# 1_1.net
KiCad netlist of a schematic drawn in Altium Designer
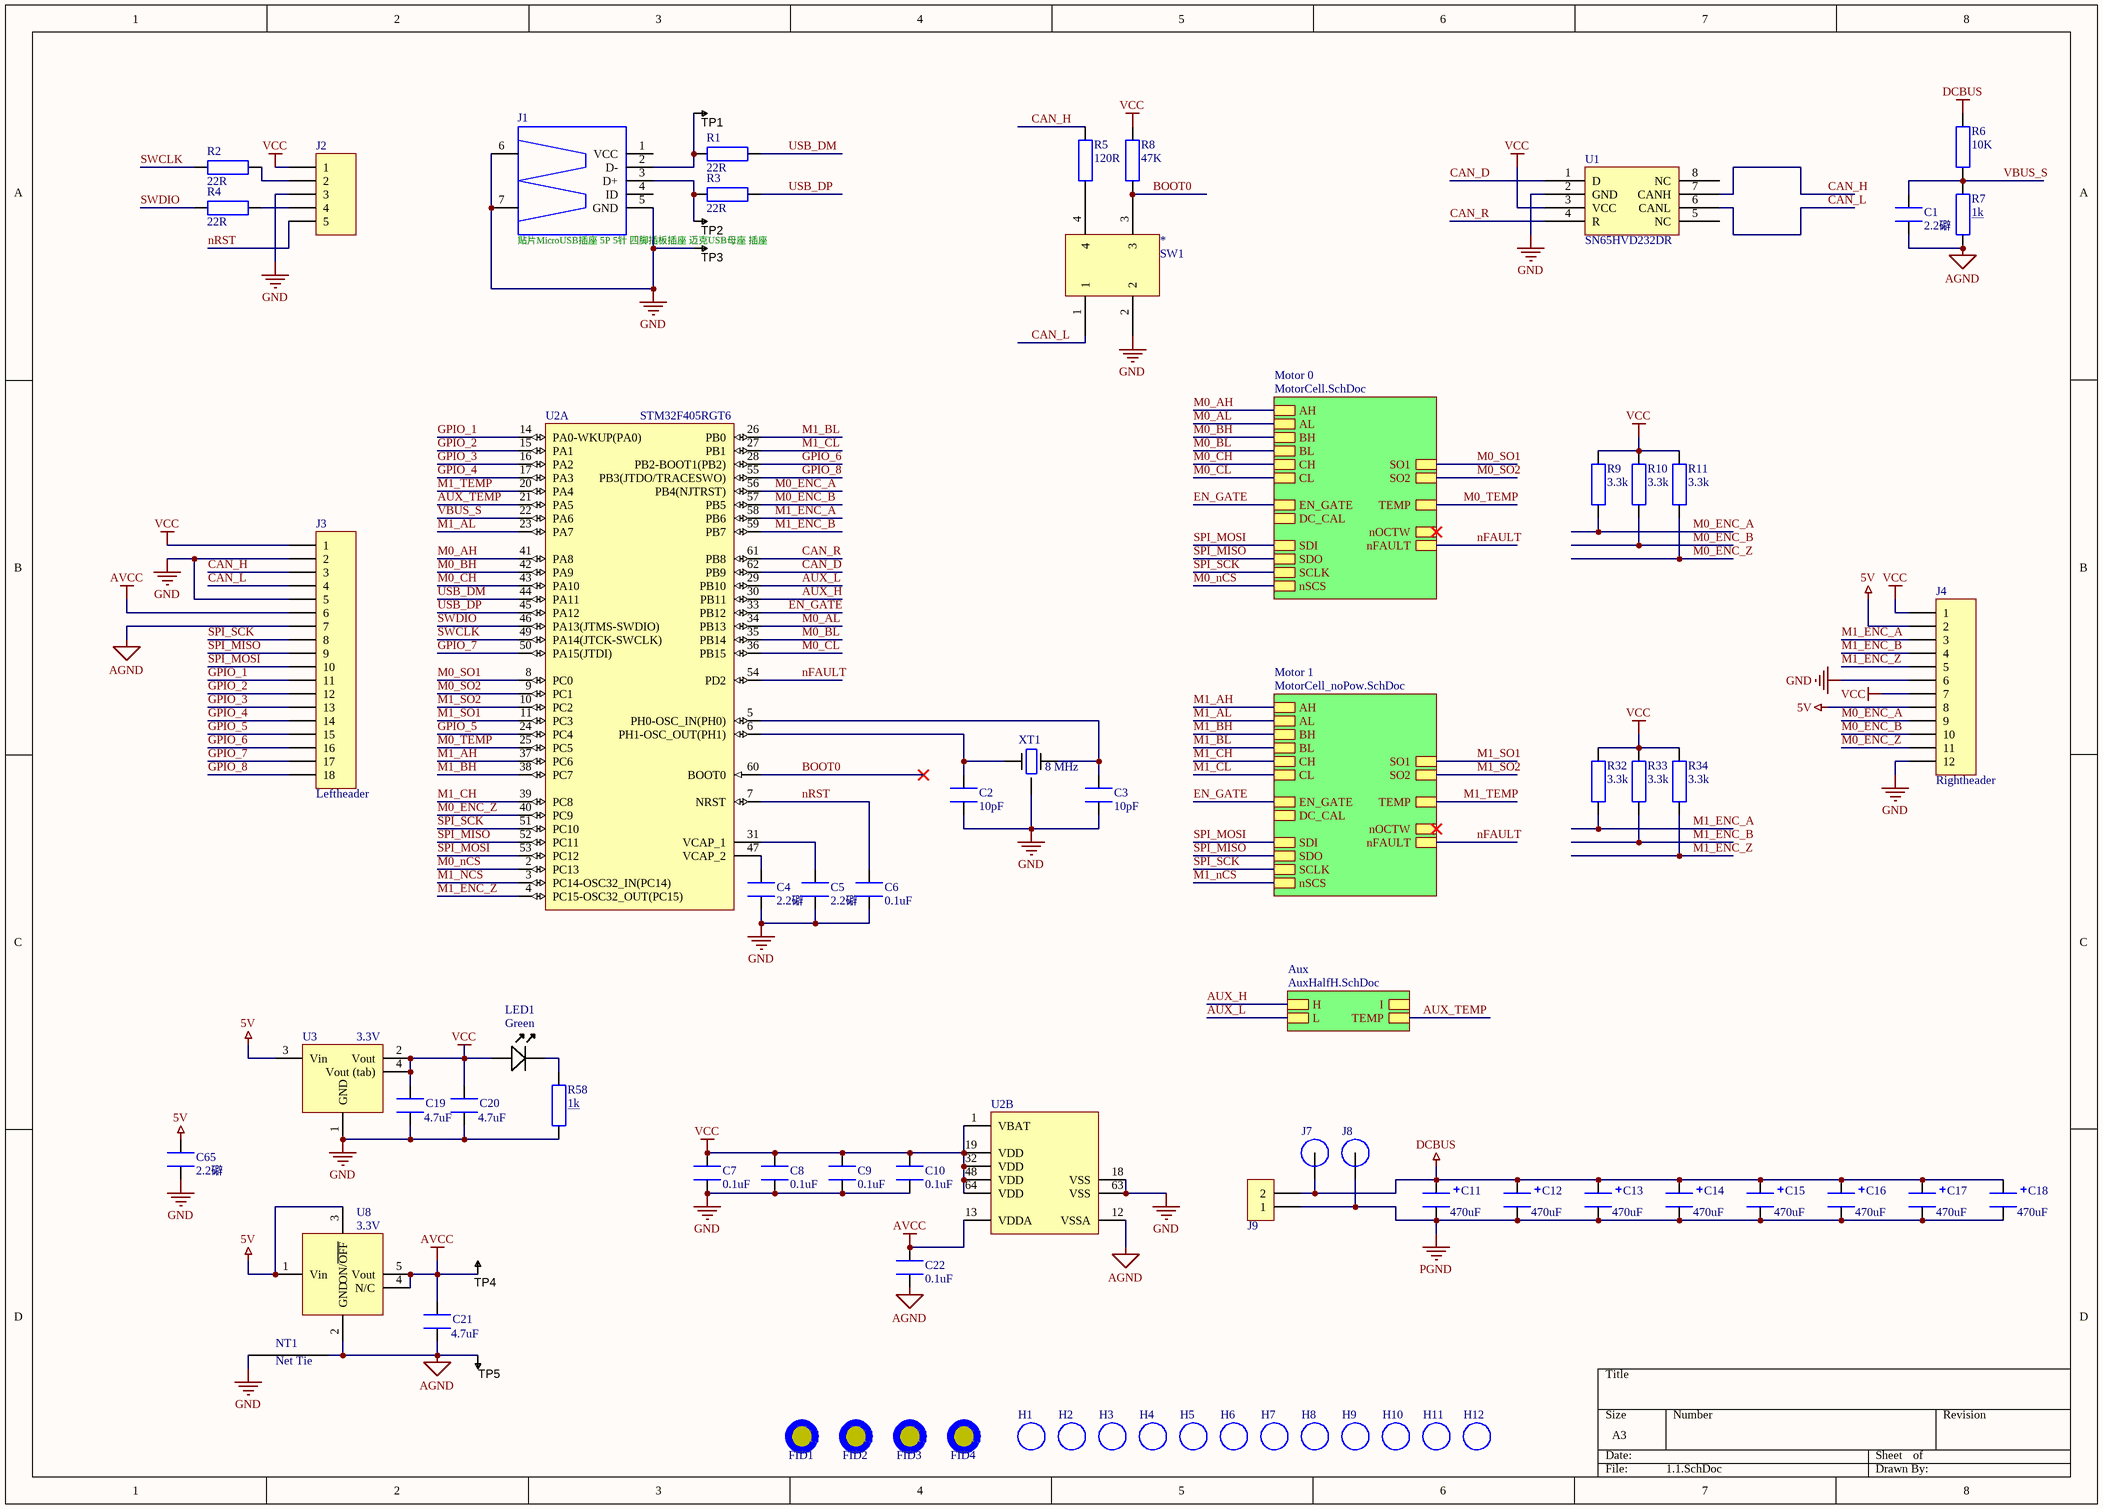
[diagram p0: 1.1.SchDoc]

(export (version "E")
  (design (tool "Eeschema 10.0.6"))
  (components
    (comp (ref "*")
      (value "SW1")
      (footprint "switch_2")
      (libsource (lib "CustomComponents") (part "Switch_2"))
    )
    (comp (ref "C1")
      (value "2.2礔")
      (footprint "CAPC1608X09L")
      (description "CAP CER 2.2UF 16V X5R 0603")
      (fields
        (field (name "MANUFACTURER") "Murata Electronics North America")
        (field (name "MANUFACTURER PART NUMBER") "GRM188R61C225KE15D")
      )
      (libsource (lib "CustomComponents") (part "GRM188R61C225KE15D"))
    )
    (comp (ref "C2")
      (value "10pF")
      (footprint "CAPC1608X09L")
      (description "CAP CER 10PF 50V NP0 0603")
      (fields
        (field (name "MANUFACTURER") "Murata Electronics North America")
        (field (name "MANUFACTURER PART NUMBER") "GRM1885C1H100JA01D")
      )
      (libsource (lib "CustomComponents") (part "GRM1885C1H100JA01D"))
    )
    (comp (ref "C3")
      (value "10pF")
      (footprint "CAPC1608X09L")
      (description "CAP CER 10PF 50V NP0 0603")
      (fields
        (field (name "MANUFACTURER") "Murata Electronics North America")
        (field (name "MANUFACTURER PART NUMBER") "GRM1885C1H100JA01D")
      )
      (libsource (lib "CustomComponents") (part "GRM1885C1H100JA01D"))
    )
    (comp (ref "C4")
      (value "2.2礔")
      (footprint "CAPC1608X09L")
      (description "CAP CER 2.2UF 16V X5R 0603")
      (fields
        (field (name "MANUFACTURER") "Murata Electronics North America")
        (field (name "MANUFACTURER PART NUMBER") "GRM188R61C225KE15D")
      )
      (libsource (lib "CustomComponents") (part "GRM188R61C225KE15D"))
    )
    (comp (ref "C5")
      (value "2.2礔")
      (footprint "CAPC1608X09L")
      (description "CAP CER 2.2UF 16V X5R 0603")
      (fields
        (field (name "MANUFACTURER") "Murata Electronics North America")
        (field (name "MANUFACTURER PART NUMBER") "GRM188R61C225KE15D")
      )
      (libsource (lib "CustomComponents") (part "GRM188R61C225KE15D"))
    )
    (comp (ref "C6")
      (value "0.1uF")
      (footprint "CAPC1608X09L")
      (description "CAP CER 0.1UF 50V X7R 0603")
      (fields
        (field (name "MANUFACTURER") "Murata Electronics North America")
        (field (name "MANUFACTURER PART NUMBER") "GRM188R71H104KA93D")
      )
      (libsource (lib "CustomComponents") (part "GRM188R71H104KA93D"))
    )
    (comp (ref "C7")
      (value "0.1uF")
      (footprint "CAPC1608X09L")
      (description "CAP CER 0.1UF 50V X7R 0603")
      (fields
        (field (name "MANUFACTURER") "Murata Electronics North America")
        (field (name "MANUFACTURER PART NUMBER") "GRM188R71H104KA93D")
      )
      (libsource (lib "CustomComponents") (part "GRM188R71H104KA93D"))
    )
    (comp (ref "C8")
      (value "0.1uF")
      (footprint "CAPC1608X09L")
      (description "CAP CER 0.1UF 50V X7R 0603")
      (fields
        (field (name "MANUFACTURER") "Murata Electronics North America")
        (field (name "MANUFACTURER PART NUMBER") "GRM188R71H104KA93D")
      )
      (libsource (lib "CustomComponents") (part "GRM188R71H104KA93D"))
    )
    (comp (ref "C9")
      (value "0.1uF")
      (footprint "CAPC1608X09L")
      (description "CAP CER 0.1UF 50V X7R 0603")
      (fields
        (field (name "MANUFACTURER") "Murata Electronics North America")
        (field (name "MANUFACTURER PART NUMBER") "GRM188R71H104KA93D")
      )
      (libsource (lib "CustomComponents") (part "GRM188R71H104KA93D"))
    )
    (comp (ref "C10")
      (value "0.1uF")
      (footprint "CAPC1608X09L")
      (description "CAP CER 0.1UF 50V X7R 0603")
      (fields
        (field (name "MANUFACTURER") "Murata Electronics North America")
        (field (name "MANUFACTURER PART NUMBER") "GRM188R71H104KA93D")
      )
      (libsource (lib "CustomComponents") (part "GRM188R71H104KA93D"))
    )
    (comp (ref "C11")
      (value "470uF")
      (footprint "CAP_ELEC_SIZE_G")
      (description "CAP, FP Series, 470 礔, 25 V, Radial Can - SMD, 10 mm")
      (fields
        (field (name "MANUFACTURER") "Panasonic Electronic Components")
        (field (name "TOLERANCE") "?0%")
      )
      (libsource (lib "CustomComponents") (part "EEEFP1E471AP"))
    )
    (comp (ref "C12")
      (value "470uF")
      (footprint "CAP_ELEC_SIZE_G")
      (description "CAP, FP Series, 470 礔, 25 V, Radial Can - SMD, 10 mm")
      (fields
        (field (name "MANUFACTURER") "Panasonic Electronic Components")
        (field (name "TOLERANCE") "?0%")
      )
      (libsource (lib "CustomComponents") (part "EEEFP1E471AP"))
    )
    (comp (ref "C13")
      (value "470uF")
      (footprint "CAP_ELEC_SIZE_G")
      (description "CAP, FP Series, 470 礔, 25 V, Radial Can - SMD, 10 mm")
      (fields
        (field (name "MANUFACTURER") "Panasonic Electronic Components")
        (field (name "TOLERANCE") "?0%")
      )
      (libsource (lib "CustomComponents") (part "EEEFP1E471AP"))
    )
    (comp (ref "C14")
      (value "470uF")
      (footprint "CAP_ELEC_SIZE_G")
      (description "CAP, FP Series, 470 礔, 25 V, Radial Can - SMD, 10 mm")
      (fields
        (field (name "MANUFACTURER") "Panasonic Electronic Components")
        (field (name "TOLERANCE") "?0%")
      )
      (libsource (lib "CustomComponents") (part "EEEFP1E471AP"))
    )
    (comp (ref "C15")
      (value "470uF")
      (footprint "CAP_ELEC_SIZE_G")
      (description "CAP, FP Series, 470 礔, 25 V, Radial Can - SMD, 10 mm")
      (fields
        (field (name "MANUFACTURER") "Panasonic Electronic Components")
        (field (name "TOLERANCE") "?0%")
      )
      (libsource (lib "CustomComponents") (part "EEEFP1E471AP"))
    )
    (comp (ref "C16")
      (value "470uF")
      (footprint "CAP_ELEC_SIZE_G")
      (description "CAP, FP Series, 470 礔, 25 V, Radial Can - SMD, 10 mm")
      (fields
        (field (name "MANUFACTURER") "Panasonic Electronic Components")
        (field (name "TOLERANCE") "?0%")
      )
      (libsource (lib "CustomComponents") (part "EEEFP1E471AP"))
    )
    (comp (ref "C17")
      (value "470uF")
      (footprint "CAP_ELEC_SIZE_G")
      (description "CAP, FP Series, 470 礔, 25 V, Radial Can - SMD, 10 mm")
      (fields
        (field (name "MANUFACTURER") "Panasonic Electronic Components")
        (field (name "TOLERANCE") "?0%")
      )
      (libsource (lib "CustomComponents") (part "EEEFP1E471AP"))
    )
    (comp (ref "C18")
      (value "470uF")
      (footprint "CAP_ELEC_SIZE_G")
      (description "CAP, FP Series, 470 礔, 25 V, Radial Can - SMD, 10 mm")
      (fields
        (field (name "MANUFACTURER") "Panasonic Electronic Components")
        (field (name "TOLERANCE") "?0%")
      )
      (libsource (lib "CustomComponents") (part "EEEFP1E471AP"))
    )
    (comp (ref "C19")
      (value "4.7uF")
      (footprint "CAPC2012X09N")
      (description "CAP CER 4.7UF 35V X5R 0805")
      (fields
        (field (name "MANUFACTURER") "Murata Electronics North America")
        (field (name "TOLERANCE") "?0%")
      )
      (libsource (lib "CustomComponents") (part "GRM219R6YA475KA73D"))
    )
    (comp (ref "C20")
      (value "4.7uF")
      (footprint "CAPC2012X09N")
      (description "CAP CER 4.7UF 35V X5R 0805")
      (fields
        (field (name "MANUFACTURER") "Murata Electronics North America")
        (field (name "TOLERANCE") "?0%")
      )
      (libsource (lib "CustomComponents") (part "GRM219R6YA475KA73D"))
    )
    (comp (ref "C21")
      (value "4.7uF")
      (footprint "CAPC2012X09N")
      (description "CAP CER 4.7UF 35V X5R 0805")
      (fields
        (field (name "MANUFACTURER") "Murata Electronics North America")
        (field (name "TOLERANCE") "?0%")
      )
      (libsource (lib "CustomComponents") (part "GRM219R6YA475KA73D"))
    )
    (comp (ref "C22")
      (value "0.1uF")
      (footprint "CAPC1608X09L")
      (description "CAP CER 0.1UF 50V X7R 0603")
      (fields
        (field (name "MANUFACTURER") "Murata Electronics North America")
        (field (name "MANUFACTURER PART NUMBER") "GRM188R71H104KA93D")
      )
      (libsource (lib "CustomComponents") (part "GRM188R71H104KA93D"))
    )
    (comp (ref "C65")
      (value "2.2礔")
      (footprint "CAPC1608X09L")
      (description "CAP CER 2.2UF 16V X5R 0603")
      (fields
        (field (name "MANUFACTURER") "Murata Electronics North America")
        (field (name "MANUFACTURER PART NUMBER") "GRM188R61C225KE15D")
      )
      (libsource (lib "CustomComponents") (part "GRM188R61C225KE15D"))
    )
    (comp (ref "FID1")
      (value "FIDUCIAL")
      (footprint "FIDUCIAL")
      (description "1mm Fiducial with 2mm soldermask, 3mm keepout")
      (libsource (lib "CustomComponents") (part "FIDUCIAL"))
    )
    (comp (ref "FID2")
      (value "FIDUCIAL")
      (footprint "FIDUCIAL")
      (description "1mm Fiducial with 2mm soldermask, 3mm keepout")
      (libsource (lib "CustomComponents") (part "FIDUCIAL"))
    )
    (comp (ref "FID3")
      (value "FIDUCIAL")
      (footprint "FIDUCIAL")
      (description "1mm Fiducial with 2mm soldermask, 3mm keepout")
      (libsource (lib "CustomComponents") (part "FIDUCIAL"))
    )
    (comp (ref "FID4")
      (value "FIDUCIAL")
      (footprint "FIDUCIAL")
      (description "1mm Fiducial with 2mm soldermask, 3mm keepout")
      (libsource (lib "CustomComponents") (part "FIDUCIAL"))
    )
    (comp (ref "H1")
      (value "~")
      (footprint "M3 Hole")
      (description "M3 Hole with no copper")
      (libsource (lib "CustomComponents") (part "M3 Hole"))
    )
    (comp (ref "H2")
      (value "~")
      (footprint "M3 Hole")
      (description "M3 Hole with no copper")
      (libsource (lib "CustomComponents") (part "M3 Hole"))
    )
    (comp (ref "H3")
      (value "~")
      (footprint "M3 Hole")
      (description "M3 Hole with no copper")
      (libsource (lib "CustomComponents") (part "M3 Hole"))
    )
    (comp (ref "H4")
      (value "~")
      (footprint "M3 Hole")
      (description "M3 Hole with no copper")
      (libsource (lib "CustomComponents") (part "M3 Hole"))
    )
    (comp (ref "H5")
      (value "~")
      (footprint "M3 Hole")
      (description "M3 Hole with no copper")
      (libsource (lib "CustomComponents") (part "M3 Hole"))
    )
    (comp (ref "H6")
      (value "~")
      (footprint "M3 Hole")
      (description "M3 Hole with no copper")
      (libsource (lib "CustomComponents") (part "M3 Hole"))
    )
    (comp (ref "H7")
      (value "~")
      (footprint "M3 Hole")
      (description "M3 Hole with no copper")
      (libsource (lib "CustomComponents") (part "M3 Hole"))
    )
    (comp (ref "H8")
      (value "~")
      (footprint "M3 Hole")
      (description "M3 Hole with no copper")
      (libsource (lib "CustomComponents") (part "M3 Hole"))
    )
    (comp (ref "H9")
      (value "~")
      (footprint "M3 Hole")
      (description "M3 Hole with no copper")
      (libsource (lib "CustomComponents") (part "M3 Hole"))
    )
    (comp (ref "H10")
      (value "~")
      (footprint "M3 Hole")
      (description "M3 Hole with no copper")
      (libsource (lib "CustomComponents") (part "M3 Hole"))
    )
    (comp (ref "H11")
      (value "~")
      (footprint "M3 Hole")
      (description "M3 Hole with no copper")
      (libsource (lib "CustomComponents") (part "M3 Hole"))
    )
    (comp (ref "H12")
      (value "~")
      (footprint "M3 Hole")
      (description "M3 Hole with no copper")
      (libsource (lib "CustomComponents") (part "M3 Hole"))
    )
    (comp (ref "J1")
      (value "贴片MicroUSB插座 5P 5针 四脚插板插座 迈克USB母座 插座")
      (footprint "Micro_USB")
      (libsource (lib "*") (part "USB_1_1"))
    )
    (comp (ref "J2")
      (value "~")
      (footprint "HDR1X5")
      (description "Header, 5-Pin")
      (fields (field (name "PUBLISHER") "Altium Limited"))
      (libsource (lib "Miscellaneous Connectors") (part "Header 5"))
    )
    (comp (ref "J3")
      (value "Leftheader")
      (footprint "HDR1X18")
      (description "Header, 18-Pin")
      (fields (field (name "PUBLISHER") "Altium Limited"))
      (libsource (lib "Miscellaneous Connectors") (part "Header 18"))
    )
    (comp (ref "J4")
      (value "Rightheader")
      (footprint "HDR1X12")
      (description "Header, 12-Pin")
      (fields (field (name "PUBLISHER") "Altium Limited"))
      (libsource (lib "Miscellaneous Connectors") (part "Header 12"))
    )
    (comp (ref "J7")
      (value "~")
      (footprint "M3 Spade Hole")
      (description "M3 Spade Terminal")
      (libsource (lib "CustomComponents") (part "M3 Spade Terminal"))
    )
    (comp (ref "J8")
      (value "~")
      (footprint "M3 Spade Hole")
      (description "M3 Spade Terminal")
      (libsource (lib "CustomComponents") (part "M3 Spade Terminal"))
    )
    (comp (ref "J9")
      (value "1868076")
      (footprint "1868076")
      (description "CONN TERM BLOCK 2POS 7.62MM")
      (fields (field (name "MANUFACTURER") "Phoenix Contact") (field (name "VOLTAGE") "300V"))
      (libsource (lib "CustomComponents") (part "1868076"))
    )
    (comp (ref "LED1")
      (value "Green")
      (footprint "LED-0603-GREEN")
      (description "LED GREEN CLEAR 0603 SMD")
      (fields
        (field (name "MANUFACTURER") "Lite-On Inc.")
        (field (name "MANUFACTURER PART NUMBER") "LTST-C190KGKT")
      )
      (libsource (lib "CustomComponents") (part "LTST-C190KGKT"))
    )
    (comp (ref "NT1")
      (value "~")
      (footprint "NetTie_2mm")
      (libsource (lib "CustomComponents") (part "NetTie_2mm"))
    )
    (comp (ref "R1")
      (value "22R")
      (footprint "RESC1608X55N")
      (description "RES SMD 22 OHM 1% 1/10W 0603")
      (fields
        (field (name "MANUFACTURER") "Yageo")
        (field (name "MANUFACTURER PART NUMBER") "RC0603FR-0722RL")
      )
      (libsource (lib "CustomComponents") (part "RC0603FR-0722RL"))
    )
    (comp (ref "R2")
      (value "22R")
      (footprint "RESC1608X55N")
      (description "RES SMD 22 OHM 1% 1/10W 0603")
      (fields
        (field (name "MANUFACTURER") "Yageo")
        (field (name "MANUFACTURER PART NUMBER") "RC0603FR-0722RL")
      )
      (libsource (lib "CustomComponents") (part "RC0603FR-0722RL"))
    )
    (comp (ref "R3")
      (value "22R")
      (footprint "RESC1608X55N")
      (description "RES SMD 22 OHM 1% 1/10W 0603")
      (fields
        (field (name "MANUFACTURER") "Yageo")
        (field (name "MANUFACTURER PART NUMBER") "RC0603FR-0722RL")
      )
      (libsource (lib "CustomComponents") (part "RC0603FR-0722RL"))
    )
    (comp (ref "R4")
      (value "22R")
      (footprint "RESC1608X55N")
      (description "RES SMD 22 OHM 1% 1/10W 0603")
      (fields
        (field (name "MANUFACTURER") "Yageo")
        (field (name "MANUFACTURER PART NUMBER") "RC0603FR-0722RL")
      )
      (libsource (lib "CustomComponents") (part "RC0603FR-0722RL"))
    )
    (comp (ref "R5")
      (value "120R")
      (footprint "RESC1608X55N")
      (description "RES SMD 120 OHM 1% 1/10W 0603")
      (fields
        (field (name "MANUFACTURER") "Yageo")
        (field (name "MANUFACTURER PART NUMBER") "RC0603FR-07120RL")
      )
      (libsource (lib "CustomComponents") (part "RC0603FR-07120RL"))
    )
    (comp (ref "R6")
      (value "10K")
      (footprint "RESC1608X55N")
      (description "RES SMD 10K OHM 1% 1/10W 0603")
      (fields
        (field (name "MANUFACTURER") "Yageo")
        (field (name "MANUFACTURER PART NUMBER") "RC0603FR-0710KL")
      )
      (libsource (lib "CustomComponents") (part "RC0603FR-0710KL"))
    )
    (comp (ref "R7")
      (value "1k")
      (footprint "RESC1608X55N")
      (description "RES SMD 1K OHM 1% 1/10W 0603")
      (fields (field (name "MANUFACTURER") "Yageo") (field (name "TOLERANCE") "?%"))
      (libsource (lib "CustomComponents") (part "RC0603FR-071KL"))
    )
    (comp (ref "R8")
      (value "47K")
      (footprint "RESC1608X55N")
      (description "RES SMD 47K OHM 1% 1/10W 0603")
      (fields
        (field (name "MANUFACTURER") "Yageo")
        (field (name "MANUFACTURER PART NUMBER") "RC0603FR-0747KL")
      )
      (libsource (lib "CustomComponents") (part "RC0603FR-0747KL"))
    )
    (comp (ref "R9")
      (value "3.3k")
      (footprint "RESC1608X55N")
      (description "RES SMD 3.3K OHM 1% 1/10W 0603")
      (fields (field (name "MANUFACTURER") "Yageo") (field (name "TOLERANCE") "?%"))
      (libsource (lib "CustomComponents") (part "RC0603FR-073K3L"))
    )
    (comp (ref "R10")
      (value "3.3k")
      (footprint "RESC1608X55N")
      (description "RES SMD 3.3K OHM 1% 1/10W 0603")
      (fields (field (name "MANUFACTURER") "Yageo") (field (name "TOLERANCE") "?%"))
      (libsource (lib "CustomComponents") (part "RC0603FR-073K3L"))
    )
    (comp (ref "R11")
      (value "3.3k")
      (footprint "RESC1608X55N")
      (description "RES SMD 3.3K OHM 1% 1/10W 0603")
      (fields (field (name "MANUFACTURER") "Yageo") (field (name "TOLERANCE") "?%"))
      (libsource (lib "CustomComponents") (part "RC0603FR-073K3L"))
    )
    (comp (ref "R32")
      (value "3.3k")
      (footprint "RESC1608X55N")
      (description "RES SMD 3.3K OHM 1% 1/10W 0603")
      (fields (field (name "MANUFACTURER") "Yageo") (field (name "TOLERANCE") "?%"))
      (libsource (lib "CustomComponents") (part "RC0603FR-073K3L"))
    )
    (comp (ref "R33")
      (value "3.3k")
      (footprint "RESC1608X55N")
      (description "RES SMD 3.3K OHM 1% 1/10W 0603")
      (fields (field (name "MANUFACTURER") "Yageo") (field (name "TOLERANCE") "?%"))
      (libsource (lib "CustomComponents") (part "RC0603FR-073K3L"))
    )
    (comp (ref "R34")
      (value "3.3k")
      (footprint "RESC1608X55N")
      (description "RES SMD 3.3K OHM 1% 1/10W 0603")
      (fields (field (name "MANUFACTURER") "Yageo") (field (name "TOLERANCE") "?%"))
      (libsource (lib "CustomComponents") (part "RC0603FR-073K3L"))
    )
    (comp (ref "R58")
      (value "1k")
      (footprint "RESC1608X55N")
      (description "RES SMD 1K OHM 1% 1/10W 0603")
      (fields (field (name "MANUFACTURER") "Yageo") (field (name "TOLERANCE") "?%"))
      (libsource (lib "CustomComponents") (part "RC0603FR-071KL"))
    )
    (comp (ref "TP1")
      (value "TESTPOINT")
      (footprint "TP-R60")
      (description "SMD test pin")
      (libsource (lib "PBL - Test Points") (part "TESTPOINT"))
    )
    (comp (ref "TP2")
      (value "TESTPOINT")
      (footprint "TP-R60")
      (description "SMD test pin")
      (libsource (lib "PBL - Test Points") (part "TESTPOINT"))
    )
    (comp (ref "TP3")
      (value "TESTPOINT")
      (footprint "TP-R60")
      (description "SMD test pin")
      (libsource (lib "PBL - Test Points") (part "TESTPOINT"))
    )
    (comp (ref "TP4")
      (value "TESTPOINT")
      (footprint "TP-R30")
      (description "SMD test pin")
      (libsource (lib "PBL - Test Points") (part "TESTPOINT"))
    )
    (comp (ref "TP5")
      (value "TESTPOINT")
      (footprint "TP-R30")
      (description "SMD test pin")
      (libsource (lib "PBL - Test Points") (part "TESTPOINT"))
    )
    (comp (ref "U1")
      (value "SN65HVD232D")
      (footprint "SOIC127P600X175-8N")
      (fields
        (field (name "MANUFACTURER") "Texas Instruments")
        (field (name "MANUFACTURER PART NUMBER") "SN65HVD232DR")
      )
      (libsource (lib "CustomComponents") (part "SN65HVD232D"))
    )
    (comp (ref "U2")
      (value "~")
      (footprint "STM-LQFP64_N")
      (fields (field (name "MANUFACTURER") "STMicroelectronics") (field (name "PARTNUMBER") "STM32F405RGT6"))
      (libsource (lib "STMicroelectronics STM32 F4") (part "STM32F405RGT6"))
    )
    (comp (ref "U3")
      (value "3.3V")
      (footprint "SOT223")
      (description "IC REG LDO 3.3V 1A SOT223")
      (fields (field (name "MANUFACTURER") "Diodes Incorporated"))
      (libsource (lib "CustomComponents") (part "AZ1117EH-3.3TRG1"))
    )
    (comp (ref "U8")
      (value "3.3V")
      (footprint "SOT23-5")
      (description "IC REG LDO 3.3V 0.25A SOT23-5")
      (fields (field (name "MANUFACTURER") "Texas Instruments"))
      (libsource (lib "CustomComponents") (part "LP5907MFX-3.3/NOPB"))
    )
    (comp (ref "XT1")
      (value "8 MHz")
      (footprint "DFN220P320X110-4N")
      (description "Crystal 8MHz ?0ppm 10pF 200 Ohm -10癈 ~ 60癈 Surface Mount 4-SMD, No Lead (DFN, LCC)")
      (fields
        (field (name "MANUFACTURER") "Abracon LLC")
        (field (name "MANUFACTURER PART NUMBER") "ABM3B-8.000MHZ-10-1-U-T")
      )
      (libsource (lib "CustomComponents") (part "ABM3B-8.000MHZ-10-1-U-T"))
    )
  )
  (nets
    (net (code "1") (name "/AUX_H") (class "Default")
      (node (ref "U2") (pin "30") (pinfunction "PB11_30") (pintype "bidirectional"))
    )
    (net (code "2") (name "/AUX_L") (class "Default")
      (node (ref "U2") (pin "29") (pinfunction "PB10_29") (pintype "bidirectional"))
    )
    (net (code "3") (name "/AUX_TEMP") (class "Default")
      (node (ref "U2") (pin "21") (pinfunction "PA5_21") (pintype "bidirectional"))
    )
    (net (code "4") (name "/BOOT0") (class "Default")
      (node (ref "*") (pin "3") (pinfunction "3_3") (pintype "passive"))
      (node (ref "R8") (pin "1") (pinfunction "0_1") (pintype "passive"))
      (node (ref "U2") (pin "60") (pinfunction "BOOT0_60") (pintype "input"))
    )
    (net (code "5") (name "/CAN_D") (class "Default")
      (node (ref "U1") (pin "1") (pinfunction "D_1") (pintype "passive"))
      (node (ref "U2") (pin "62") (pinfunction "PB9_62") (pintype "bidirectional"))
    )
    (net (code "6") (name "/CAN_H") (class "Default")
      (node (ref "J3") (pin "3") (pinfunction "3_3") (pintype "passive"))
      (node (ref "R5") (pin "2") (pinfunction "0_2") (pintype "passive"))
      (node (ref "U1") (pin "7") (pinfunction "CANH_7") (pintype "passive"))
    )
    (net (code "7") (name "/CAN_L") (class "Default")
      (node (ref "*") (pin "1") (pinfunction "1_1") (pintype "passive"))
      (node (ref "J3") (pin "4") (pinfunction "4_4") (pintype "passive"))
      (node (ref "U1") (pin "6") (pinfunction "CANL_6") (pintype "passive"))
    )
    (net (code "8") (name "/CAN_R") (class "Default")
      (node (ref "U1") (pin "4") (pinfunction "R_4") (pintype "passive"))
      (node (ref "U2") (pin "61") (pinfunction "PB8_61") (pintype "bidirectional"))
    )
    (net (code "11") (name "/EN_GATE") (class "Default")
      (node (ref "U2") (pin "33") (pinfunction "PB12_33") (pintype "bidirectional"))
    )
    (net (code "12") (name "/GPIO_1") (class "Default")
      (node (ref "J3") (pin "11") (pinfunction "11_11") (pintype "passive"))
      (node (ref "U2") (pin "14") (pinfunction "PA0-WKUP(PA0)_14") (pintype "bidirectional"))
    )
    (net (code "13") (name "/GPIO_2") (class "Default")
      (node (ref "J3") (pin "12") (pinfunction "12_12") (pintype "passive"))
      (node (ref "U2") (pin "15") (pinfunction "PA1_15") (pintype "bidirectional"))
    )
    (net (code "14") (name "/GPIO_3") (class "Default")
      (node (ref "J3") (pin "13") (pinfunction "13_13") (pintype "passive"))
      (node (ref "U2") (pin "16") (pinfunction "PA2_16") (pintype "bidirectional"))
    )
    (net (code "15") (name "/GPIO_4") (class "Default")
      (node (ref "J3") (pin "14") (pinfunction "14_14") (pintype "passive"))
      (node (ref "U2") (pin "17") (pinfunction "PA3_17") (pintype "bidirectional"))
    )
    (net (code "16") (name "/GPIO_5") (class "Default")
      (node (ref "J3") (pin "15") (pinfunction "15_15") (pintype "passive"))
      (node (ref "U2") (pin "24") (pinfunction "PC4_24") (pintype "bidirectional"))
    )
    (net (code "17") (name "/GPIO_6") (class "Default")
      (node (ref "J3") (pin "16") (pinfunction "16_16") (pintype "passive"))
      (node (ref "U2") (pin "28") (pinfunction "PB2-BOOT1(PB2)_28") (pintype "bidirectional"))
    )
    (net (code "18") (name "/GPIO_7") (class "Default")
      (node (ref "J3") (pin "17") (pinfunction "17_17") (pintype "passive"))
      (node (ref "U2") (pin "50") (pinfunction "PA15(JTDI)_50") (pintype "bidirectional"))
    )
    (net (code "19") (name "/GPIO_8") (class "Default")
      (node (ref "J3") (pin "18") (pinfunction "18_18") (pintype "passive"))
      (node (ref "U2") (pin "55") (pinfunction "PB3(JTDO/TRACESWO)_55") (pintype "bidirectional"))
    )
    (net (code "21") (name "/M0_AH") (class "Default")
      (node (ref "U2") (pin "41") (pinfunction "PA8_41") (pintype "bidirectional"))
    )
    (net (code "22") (name "/M0_AL") (class "Default")
      (node (ref "U2") (pin "34") (pinfunction "PB13_34") (pintype "bidirectional"))
    )
    (net (code "23") (name "/M0_BH") (class "Default")
      (node (ref "U2") (pin "42") (pinfunction "PA9_42") (pintype "bidirectional"))
    )
    (net (code "24") (name "/M0_BL") (class "Default")
      (node (ref "U2") (pin "35") (pinfunction "PB14_35") (pintype "bidirectional"))
    )
    (net (code "25") (name "/M0_CH") (class "Default")
      (node (ref "U2") (pin "43") (pinfunction "PA10_43") (pintype "bidirectional"))
    )
    (net (code "26") (name "/M0_CL") (class "Default")
      (node (ref "U2") (pin "36") (pinfunction "PB15_36") (pintype "bidirectional"))
    )
    (net (code "27") (name "/M0_ENC_A") (class "Default")
      (node (ref "J4") (pin "9") (pinfunction "9_9") (pintype "passive"))
      (node (ref "R9") (pin "1") (pinfunction "0_1") (pintype "passive"))
      (node (ref "U2") (pin "56") (pinfunction "PB4(NJTRST)_56") (pintype "bidirectional"))
    )
    (net (code "28") (name "/M0_ENC_B") (class "Default")
      (node (ref "J4") (pin "10") (pinfunction "10_10") (pintype "passive"))
      (node (ref "R10") (pin "1") (pinfunction "0_1") (pintype "passive"))
      (node (ref "U2") (pin "57") (pinfunction "PB5_57") (pintype "bidirectional"))
    )
    (net (code "29") (name "/M0_ENC_Z") (class "Default")
      (node (ref "J4") (pin "11") (pinfunction "11_11") (pintype "passive"))
      (node (ref "R11") (pin "1") (pinfunction "0_1") (pintype "passive"))
      (node (ref "U2") (pin "40") (pinfunction "PC9_40") (pintype "bidirectional"))
    )
    (net (code "30") (name "/M0_SO1") (class "Default")
      (node (ref "U2") (pin "8") (pinfunction "PC0_8") (pintype "bidirectional"))
    )
    (net (code "31") (name "/M0_SO2") (class "Default")
      (node (ref "U2") (pin "9") (pinfunction "PC1_9") (pintype "bidirectional"))
    )
    (net (code "32") (name "/M0_TEMP") (class "Default")
      (node (ref "U2") (pin "25") (pinfunction "PC5_25") (pintype "bidirectional"))
    )
    (net (code "33") (name "/M0_nCS") (class "Default")
      (node (ref "U2") (pin "2") (pinfunction "PC13_2") (pintype "bidirectional"))
    )
    (net (code "34") (name "/M1_AH") (class "Default")
      (node (ref "U2") (pin "37") (pinfunction "PC6_37") (pintype "bidirectional"))
    )
    (net (code "35") (name "/M1_AL") (class "Default")
      (node (ref "U2") (pin "23") (pinfunction "PA7_23") (pintype "bidirectional"))
    )
    (net (code "36") (name "/M1_BH") (class "Default")
      (node (ref "U2") (pin "38") (pinfunction "PC7_38") (pintype "bidirectional"))
    )
    (net (code "37") (name "/M1_BL") (class "Default")
      (node (ref "U2") (pin "26") (pinfunction "PB0_26") (pintype "bidirectional"))
    )
    (net (code "38") (name "/M1_CH") (class "Default")
      (node (ref "U2") (pin "39") (pinfunction "PC8_39") (pintype "bidirectional"))
    )
    (net (code "39") (name "/M1_CL") (class "Default")
      (node (ref "U2") (pin "27") (pinfunction "PB1_27") (pintype "bidirectional"))
    )
    (net (code "40") (name "/M1_ENC_A") (class "Default")
      (node (ref "J4") (pin "3") (pinfunction "3_3") (pintype "passive"))
      (node (ref "R32") (pin "2") (pinfunction "0_2") (pintype "passive"))
      (node (ref "U2") (pin "58") (pinfunction "PB6_58") (pintype "bidirectional"))
    )
    (net (code "41") (name "/M1_ENC_B") (class "Default")
      (node (ref "J4") (pin "4") (pinfunction "4_4") (pintype "passive"))
      (node (ref "R33") (pin "2") (pinfunction "0_2") (pintype "passive"))
      (node (ref "U2") (pin "59") (pinfunction "PB7_59") (pintype "bidirectional"))
    )
    (net (code "42") (name "/M1_ENC_Z") (class "Default")
      (node (ref "J4") (pin "5") (pinfunction "5_5") (pintype "passive"))
      (node (ref "R34") (pin "2") (pinfunction "0_2") (pintype "passive"))
      (node (ref "U2") (pin "4") (pinfunction "PC15-OSC32_OUT(PC15)_4") (pintype "bidirectional"))
    )
    (net (code "43") (name "/M1_NCS") (class "Default")
      (node (ref "U2") (pin "3") (pinfunction "PC14-OSC32_IN(PC14)_3") (pintype "bidirectional"))
    )
    (net (code "44") (name "/M1_SO1") (class "Default")
      (node (ref "U2") (pin "11") (pinfunction "PC3_11") (pintype "bidirectional"))
    )
    (net (code "45") (name "/M1_SO2") (class "Default")
      (node (ref "U2") (pin "10") (pinfunction "PC2_10") (pintype "bidirectional"))
    )
    (net (code "46") (name "/M1_TEMP") (class "Default")
      (node (ref "U2") (pin "20") (pinfunction "PA4_20") (pintype "bidirectional"))
    )
    (net (code "48") (name "/SPI_MISO") (class "Default")
      (node (ref "J3") (pin "9") (pinfunction "9_9") (pintype "passive"))
      (node (ref "U2") (pin "52") (pinfunction "PC11_52") (pintype "bidirectional"))
    )
    (net (code "49") (name "/SPI_MOSI") (class "Default")
      (node (ref "J3") (pin "10") (pinfunction "10_10") (pintype "passive"))
      (node (ref "U2") (pin "53") (pinfunction "PC12_53") (pintype "bidirectional"))
    )
    (net (code "50") (name "/SPI_SCK") (class "Default")
      (node (ref "J3") (pin "8") (pinfunction "8_8") (pintype "passive"))
      (node (ref "U2") (pin "51") (pinfunction "PC10_51") (pintype "bidirectional"))
    )
    (net (code "51") (name "/SWCLK") (class "Default")
      (node (ref "R2") (pin "2") (pinfunction "0_2") (pintype "passive"))
      (node (ref "U2") (pin "49") (pinfunction "PA14(JTCK-SWCLK)_49") (pintype "bidirectional"))
    )
    (net (code "52") (name "/SWDIO") (class "Default")
      (node (ref "R4") (pin "2") (pinfunction "0_2") (pintype "passive"))
      (node (ref "U2") (pin "46") (pinfunction "PA13(JTMS-SWDIO)_46") (pintype "bidirectional"))
    )
    (net (code "53") (name "/USB_DM") (class "Default")
      (node (ref "R1") (pin "1") (pinfunction "0_1") (pintype "passive"))
      (node (ref "U2") (pin "44") (pinfunction "PA11_44") (pintype "bidirectional"))
    )
    (net (code "54") (name "/USB_DP") (class "Default")
      (node (ref "R3") (pin "1") (pinfunction "0_1") (pintype "passive"))
      (node (ref "U2") (pin "45") (pinfunction "PA12_45") (pintype "bidirectional"))
    )
    (net (code "55") (name "/VBUS_S") (class "Default")
      (node (ref "C1") (pin "2") (pinfunction "2_2") (pintype "passive"))
      (node (ref "R6") (pin "1") (pinfunction "0_1") (pintype "passive"))
      (node (ref "R7") (pin "2") (pinfunction "0_2") (pintype "passive"))
      (node (ref "U2") (pin "22") (pinfunction "PA6_22") (pintype "bidirectional"))
    )
    (net (code "56") (name "/nFAULT") (class "Default")
      (node (ref "U2") (pin "54") (pinfunction "PD2_54") (pintype "bidirectional"))
    )
    (net (code "59") (name "/nRST") (class "Default")
      (node (ref "C6") (pin "2") (pinfunction "2_2") (pintype "passive"))
      (node (ref "J2") (pin "5") (pinfunction "5_5") (pintype "passive"))
      (node (ref "U2") (pin "7") (pinfunction "NRST_7") (pintype "bidirectional"))
    )
    (net (code "60") (name "5V") (class "Default")
      (node (ref "C65") (pin "2") (pinfunction "2_2") (pintype "passive"))
      (node (ref "J4") (pin "2") (pinfunction "2_2") (pintype "passive"))
      (node (ref "J4") (pin "8") (pinfunction "8_8") (pintype "passive"))
      (node (ref "U3") (pin "3") (pinfunction "Vin_3") (pintype "passive"))
      (node (ref "U8") (pin "1") (pinfunction "Vin_1") (pintype "passive"))
      (node (ref "U8") (pin "3") (pinfunction "ON/~{OFF}_3") (pintype "passive"))
    )
    (net (code "61") (name "AGND") (class "Default")
      (node (ref "C1") (pin "1") (pinfunction "1_1") (pintype "passive"))
      (node (ref "C21") (pin "1") (pinfunction "1_1") (pintype "passive"))
      (node (ref "C22") (pin "2") (pinfunction "2_2") (pintype "passive"))
      (node (ref "J3") (pin "7") (pinfunction "7_7") (pintype "passive"))
      (node (ref "NT1") (pin "2") (pintype "passive"))
      (node (ref "R7") (pin "1") (pinfunction "0_1") (pintype "passive"))
      (node (ref "TP5") (pin "1") (pintype "passive"))
      (node (ref "U2") (pin "12") (pinfunction "VSSA_12") (pintype "power_in"))
      (node (ref "U8") (pin "2") (pinfunction "GND_2") (pintype "passive"))
    )
    (net (code "62") (name "AVCC") (class "Default")
      (node (ref "C21") (pin "2") (pinfunction "2_2") (pintype "passive"))
      (node (ref "C22") (pin "1") (pinfunction "1_1") (pintype "passive"))
      (node (ref "J3") (pin "6") (pinfunction "6_6") (pintype "passive"))
      (node (ref "TP4") (pin "1") (pintype "passive"))
      (node (ref "U2") (pin "13") (pinfunction "VDDA_13") (pintype "power_in"))
      (node (ref "U8") (pin "4") (pinfunction "N/C_4") (pintype "passive"))
      (node (ref "U8") (pin "5") (pinfunction "Vout_5") (pintype "passive"))
    )
    (net (code "63") (name "DCBUS") (class "Default")
      (node (ref "C11") (pin "1") (pinfunction "1_1") (pintype "passive"))
      (node (ref "C12") (pin "1") (pinfunction "1_1") (pintype "passive"))
      (node (ref "C13") (pin "1") (pinfunction "1_1") (pintype "passive"))
      (node (ref "C14") (pin "1") (pinfunction "1_1") (pintype "passive"))
      (node (ref "C15") (pin "1") (pinfunction "1_1") (pintype "passive"))
      (node (ref "C16") (pin "1") (pinfunction "1_1") (pintype "passive"))
      (node (ref "C17") (pin "1") (pinfunction "1_1") (pintype "passive"))
      (node (ref "C18") (pin "1") (pinfunction "1_1") (pintype "passive"))
      (node (ref "J7") (pin "1") (pinfunction "1_1") (pintype "passive"))
      (node (ref "J9") (pin "2") (pinfunction "2_2") (pintype "passive"))
      (node (ref "R6") (pin "2") (pinfunction "0_2") (pintype "passive"))
    )
    (net (code "64") (name "GND") (class "Default")
      (node (ref "*") (pin "2") (pinfunction "2_2") (pintype "passive"))
      (node (ref "C10") (pin "2") (pinfunction "2_2") (pintype "passive"))
      (node (ref "C19") (pin "1") (pinfunction "1_1") (pintype "passive"))
      (node (ref "C2") (pin "2") (pinfunction "2_2") (pintype "passive"))
      (node (ref "C20") (pin "1") (pinfunction "1_1") (pintype "passive"))
      (node (ref "C3") (pin "2") (pinfunction "2_2") (pintype "passive"))
      (node (ref "C4") (pin "1") (pinfunction "1_1") (pintype "passive"))
      (node (ref "C5") (pin "1") (pinfunction "1_1") (pintype "passive"))
      (node (ref "C6") (pin "1") (pinfunction "1_1") (pintype "passive"))
      (node (ref "C65") (pin "1") (pinfunction "1_1") (pintype "passive"))
      (node (ref "C7") (pin "2") (pinfunction "2_2") (pintype "passive"))
      (node (ref "C8") (pin "2") (pinfunction "2_2") (pintype "passive"))
      (node (ref "C9") (pin "2") (pinfunction "2_2") (pintype "passive"))
      (node (ref "J1") (pin "5") (pinfunction "GND_5") (pintype "passive"))
      (node (ref "J1") (pin "6") (pinfunction "6_6") (pintype "passive"))
      (node (ref "J1") (pin "7") (pinfunction "7_7") (pintype "passive"))
      (node (ref "J2") (pin "3") (pinfunction "3_3") (pintype "passive"))
      (node (ref "J3") (pin "2") (pinfunction "2_2") (pintype "passive"))
      (node (ref "J3") (pin "5") (pinfunction "5_5") (pintype "passive"))
      (node (ref "J4") (pin "12") (pinfunction "12_12") (pintype "passive"))
      (node (ref "J4") (pin "6") (pinfunction "6_6") (pintype "passive"))
      (node (ref "NT1") (pin "1") (pintype "passive"))
      (node (ref "R58") (pin "2") (pinfunction "0_2") (pintype "passive"))
      (node (ref "TP3") (pin "1") (pintype "passive"))
      (node (ref "U1") (pin "2") (pinfunction "GND_2") (pintype "passive"))
      (node (ref "U2") (pin "18") (pinfunction "VSS_18") (pintype "power_in"))
      (node (ref "U2") (pin "63") (pinfunction "VSS_63") (pintype "power_in"))
      (node (ref "U3") (pin "1") (pinfunction "GND_1") (pintype "passive"))
      (node (ref "XT1") (pin "G") (pintype "passive"))
    )
    (net (code "65") (name "Net-(*-Pad4)") (class "Default")
      (node (ref "*") (pin "4") (pinfunction "4_4") (pintype "passive"))
      (node (ref "R5") (pin "1") (pinfunction "0_1") (pintype "passive"))
    )
    (net (code "66") (name "Net-(J1-D+)") (class "Default")
      (node (ref "J1") (pin "3") (pinfunction "D+_3") (pintype "passive"))
      (node (ref "R3") (pin "2") (pinfunction "0_2") (pintype "passive"))
      (node (ref "TP2") (pin "1") (pintype "passive"))
    )
    (net (code "67") (name "Net-(J1-D-)") (class "Default")
      (node (ref "J1") (pin "2") (pinfunction "D-_2") (pintype "passive"))
      (node (ref "R1") (pin "2") (pinfunction "0_2") (pintype "passive"))
      (node (ref "TP1") (pin "1") (pintype "passive"))
    )
    (net (code "68") (name "Net-(J2-Pad2)") (class "Default")
      (node (ref "J2") (pin "2") (pinfunction "2_2") (pintype "passive"))
      (node (ref "R2") (pin "1") (pinfunction "0_1") (pintype "passive"))
    )
    (net (code "69") (name "Net-(J2-Pad4)") (class "Default")
      (node (ref "J2") (pin "4") (pinfunction "4_4") (pintype "passive"))
      (node (ref "R4") (pin "1") (pinfunction "0_1") (pintype "passive"))
    )
    (net (code "70") (name "Net-(LED1-PadK)") (class "Default")
      (node (ref "LED1") (pin "K") (pinfunction "K_K") (pintype "passive"))
      (node (ref "R58") (pin "1") (pinfunction "0_1") (pintype "passive"))
    )
    (net (code "71") (name "Net-(U2A-PH0-OSC_IN(PH0))") (class "Default")
      (node (ref "C3") (pin "1") (pinfunction "1_1") (pintype "passive"))
      (node (ref "U2") (pin "5") (pinfunction "PH0-OSC_IN(PH0)_5") (pintype "bidirectional"))
      (node (ref "XT1") (pin "3") (pintype "passive"))
    )
    (net (code "72") (name "Net-(U2A-PH1-OSC_OUT(PH1))") (class "Default")
      (node (ref "C2") (pin "1") (pinfunction "1_1") (pintype "passive"))
      (node (ref "U2") (pin "6") (pinfunction "PH1-OSC_OUT(PH1)_6") (pintype "bidirectional"))
      (node (ref "XT1") (pin "1") (pintype "passive"))
    )
    (net (code "73") (name "Net-(U2A-VCAP_1)") (class "Default")
      (node (ref "C5") (pin "2") (pinfunction "2_2") (pintype "passive"))
      (node (ref "U2") (pin "31") (pinfunction "VCAP_1_31") (pintype "power_in"))
    )
    (net (code "74") (name "Net-(U2A-VCAP_2)") (class "Default")
      (node (ref "C4") (pin "2") (pinfunction "2_2") (pintype "passive"))
      (node (ref "U2") (pin "47") (pinfunction "VCAP_2_47") (pintype "power_in"))
    )
    (net (code "75") (name "PGND") (class "Default")
      (node (ref "C11") (pin "2") (pinfunction "2_2") (pintype "passive"))
      (node (ref "C12") (pin "2") (pinfunction "2_2") (pintype "passive"))
      (node (ref "C13") (pin "2") (pinfunction "2_2") (pintype "passive"))
      (node (ref "C14") (pin "2") (pinfunction "2_2") (pintype "passive"))
      (node (ref "C15") (pin "2") (pinfunction "2_2") (pintype "passive"))
      (node (ref "C16") (pin "2") (pinfunction "2_2") (pintype "passive"))
      (node (ref "C17") (pin "2") (pinfunction "2_2") (pintype "passive"))
      (node (ref "C18") (pin "2") (pinfunction "2_2") (pintype "passive"))
      (node (ref "J8") (pin "1") (pinfunction "1_1") (pintype "passive"))
      (node (ref "J9") (pin "1") (pinfunction "1_1") (pintype "passive"))
    )
    (net (code "76") (name "VCC") (class "Default")
      (node (ref "C10") (pin "1") (pinfunction "1_1") (pintype "passive"))
      (node (ref "C19") (pin "2") (pinfunction "2_2") (pintype "passive"))
      (node (ref "C20") (pin "2") (pinfunction "2_2") (pintype "passive"))
      (node (ref "C7") (pin "1") (pinfunction "1_1") (pintype "passive"))
      (node (ref "C8") (pin "1") (pinfunction "1_1") (pintype "passive"))
      (node (ref "C9") (pin "1") (pinfunction "1_1") (pintype "passive"))
      (node (ref "J2") (pin "1") (pinfunction "1_1") (pintype "passive"))
      (node (ref "J3") (pin "1") (pinfunction "1_1") (pintype "passive"))
      (node (ref "J4") (pin "1") (pinfunction "1_1") (pintype "passive"))
      (node (ref "J4") (pin "7") (pinfunction "7_7") (pintype "passive"))
      (node (ref "LED1") (pin "A") (pinfunction "A_A") (pintype "passive"))
      (node (ref "R10") (pin "2") (pinfunction "0_2") (pintype "passive"))
      (node (ref "R11") (pin "2") (pinfunction "0_2") (pintype "passive"))
      (node (ref "R32") (pin "1") (pinfunction "0_1") (pintype "passive"))
      (node (ref "R33") (pin "1") (pinfunction "0_1") (pintype "passive"))
      (node (ref "R34") (pin "1") (pinfunction "0_1") (pintype "passive"))
      (node (ref "R8") (pin "2") (pinfunction "0_2") (pintype "passive"))
      (node (ref "R9") (pin "2") (pinfunction "0_2") (pintype "passive"))
      (node (ref "U1") (pin "3") (pinfunction "VCC_3") (pintype "passive"))
      (node (ref "U2") (pin "1") (pinfunction "VBAT_1") (pintype "power_in"))
      (node (ref "U2") (pin "19") (pinfunction "VDD_19") (pintype "power_in"))
      (node (ref "U2") (pin "32") (pinfunction "VDD_32") (pintype "power_in"))
      (node (ref "U2") (pin "48") (pinfunction "VDD_48") (pintype "power_in"))
      (node (ref "U2") (pin "64") (pinfunction "VDD_64") (pintype "power_in"))
      (node (ref "U3") (pin "2") (pinfunction "Vout_2") (pintype "passive"))
      (node (ref "U3") (pin "4") (pinfunction "Vout_(tab)_4") (pintype "passive"))
    )
    (net (code "77") (name "unconnected-(J1-ID-Pad4)") (class "Default")
      (node (ref "J1") (pin "4") (pinfunction "ID_4") (pintype "passive"))
    )
    (net (code "78") (name "unconnected-(J1-VCC-Pad1)") (class "Default")
      (node (ref "J1") (pin "1") (pinfunction "VCC_1") (pintype "passive"))
    )
    (net (code "79") (name "unconnected-(U1-NC-Pad5)") (class "Default")
      (node (ref "U1") (pin "5") (pinfunction "NC_5") (pintype "passive"))
    )
    (net (code "80") (name "unconnected-(U1-NC-Pad8)") (class "Default")
      (node (ref "U1") (pin "8") (pinfunction "NC_8") (pintype "passive"))
    )
  )
)
